# RasPi-BplusHAT.net
KiCad netlist of a schematic drawn in EAGLE
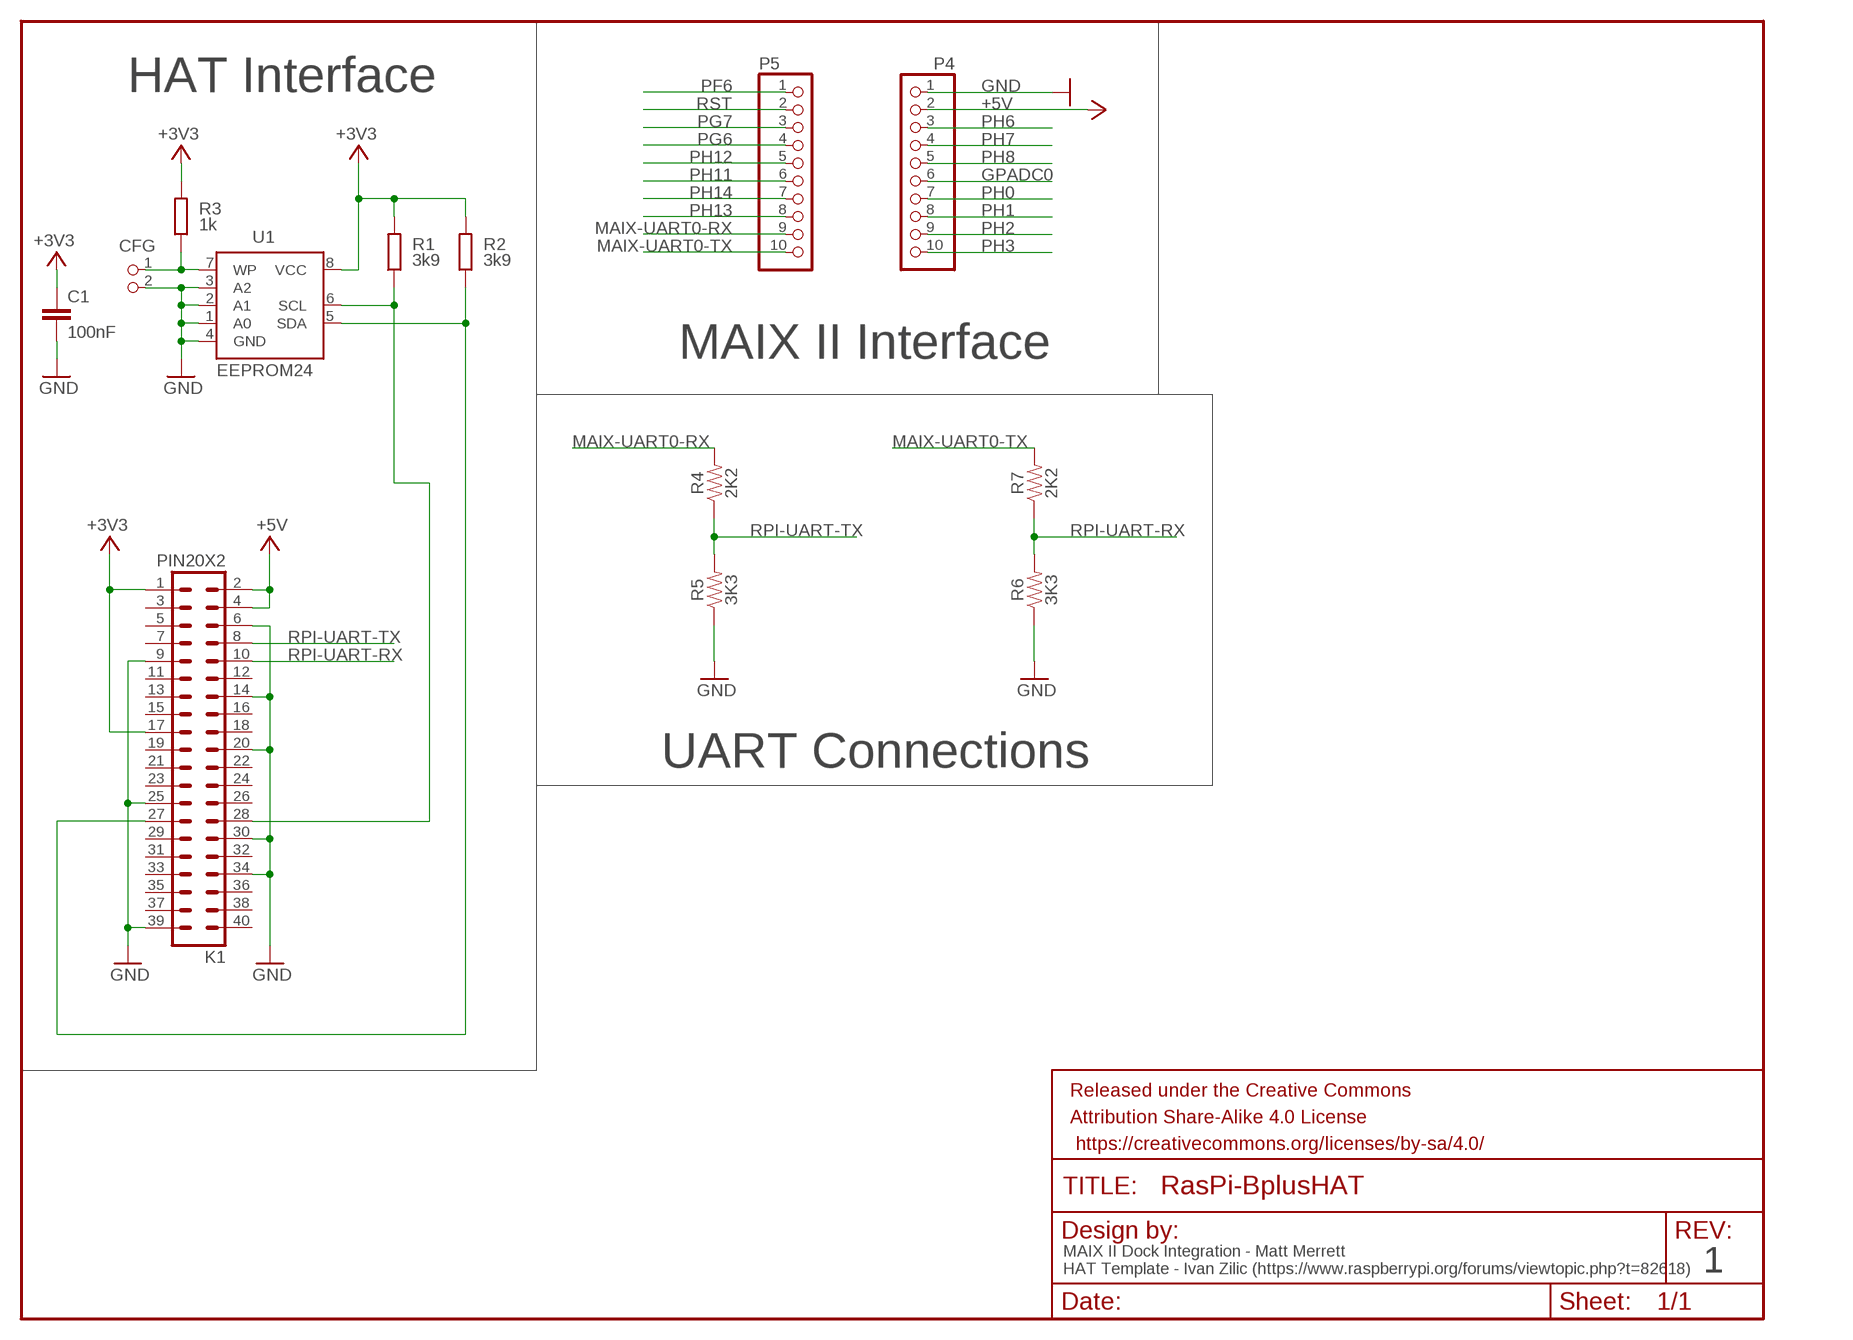
[diagram p0: schematic, sheet 1]

(export (version "E")
  (design (tool "Eeschema 10.0.6"))
  (components
    (comp (ref "C1")
      (value "100nF")
      (footprint "eagle-import:C0805K")
      (libsource (lib "eagle-import") (part "C-EUC0805K"))
    )
    (comp (ref "CFG")
      (value "PIN2_100")
      (footprint "eagle-import:PIN_W_2")
      (libsource (lib "eagle-import") (part "PIN2_100"))
    )
    (comp (ref "FRAME1")
      (value "FRAME-LETTER")
      (footprint "eagle-import:CREATIVE_COMMONS")
      (libsource (lib "eagle-import") (part "FRAME-LETTER"))
    )
    (comp (ref "K1")
      (value "PIN20X2")
      (footprint "eagle-import:PIN_20X2")
      (libsource (lib "eagle-import") (part "PIN20X2"))
    )
    (comp (ref "P4")
      (value "PINHD-1X10")
      (footprint "eagle-import:1X10")
      (libsource (lib "eagle-import") (part "PINHD-1X10"))
    )
    (comp (ref "P5")
      (value "PINHD-1X10")
      (footprint "eagle-import:1X10")
      (libsource (lib "eagle-import") (part "PINHD-1X10"))
    )
    (comp (ref "R1")
      (value "3k9")
      (footprint "eagle-import:M0805")
      (fields (field (name "TOLERANCE") "5%"))
      (libsource (lib "eagle-import") (part "R-EU_M0805"))
    )
    (comp (ref "R2")
      (value "3k9")
      (footprint "eagle-import:M0805")
      (fields (field (name "TOLERANCE") "5%"))
      (libsource (lib "eagle-import") (part "R-EU_M0805"))
    )
    (comp (ref "R3")
      (value "1k")
      (footprint "eagle-import:M0805")
      (fields (field (name "TOLERANCE") "5%"))
      (libsource (lib "eagle-import") (part "R-EU_M0805"))
    )
    (comp (ref "R4")
      (value "2K2")
      (footprint "eagle-import:AXIAL-0.3")
      (libsource (lib "eagle-import") (part "RESISTORAXIAL-0.3"))
    )
    (comp (ref "R5")
      (value "3K3")
      (footprint "eagle-import:AXIAL-0.3")
      (libsource (lib "eagle-import") (part "RESISTORAXIAL-0.3"))
    )
    (comp (ref "R6")
      (value "3K3")
      (footprint "eagle-import:AXIAL-0.3")
      (libsource (lib "eagle-import") (part "RESISTORAXIAL-0.3"))
    )
    (comp (ref "R7")
      (value "2K2")
      (footprint "eagle-import:AXIAL-0.3")
      (libsource (lib "eagle-import") (part "RESISTORAXIAL-0.3"))
    )
    (comp (ref "U1")
      (value "EEPROM24")
      (footprint "eagle-import:SOIC8")
      (libsource (lib "eagle-import") (part "EEPROM24"))
    )
  )
  (nets
    (net (code "1") (name "+3V3") (class "Default")
      (node (ref "C1") (pin "1") (pinfunction "1_1") (pintype "passive"))
      (node (ref "K1") (pin "1") (pinfunction "1_1") (pintype "passive"))
      (node (ref "K1") (pin "17") (pinfunction "17_17") (pintype "passive"))
      (node (ref "R1") (pin "2") (pinfunction "2_2") (pintype "passive"))
      (node (ref "R2") (pin "2") (pinfunction "2_2") (pintype "passive"))
      (node (ref "R3") (pin "2") (pinfunction "2_2") (pintype "passive"))
      (node (ref "U1") (pin "8") (pinfunction "VCC_8") (pintype "power_in"))
    )
    (net (code "2") (name "+5V") (class "Default")
      (node (ref "K1") (pin "2") (pinfunction "2_2") (pintype "passive"))
      (node (ref "K1") (pin "4") (pinfunction "4_4") (pintype "passive"))
      (node (ref "P4") (pin "2") (pinfunction "2_2") (pintype "passive"))
    )
    (net (code "3") (name "/GPADC0") (class "Default")
      (node (ref "P4") (pin "6") (pinfunction "6_6") (pintype "passive"))
    )
    (net (code "4") (name "/MAIX-UART0-RX") (class "Default")
      (node (ref "P5") (pin "9") (pinfunction "9_9") (pintype "passive"))
      (node (ref "R4") (pin "P$2") (pinfunction "2_P$2") (pintype "passive"))
    )
    (net (code "5") (name "/MAIX-UART0-TX") (class "Default")
      (node (ref "P5") (pin "10") (pinfunction "10_10") (pintype "passive"))
      (node (ref "R7") (pin "P$2") (pinfunction "2_P$2") (pintype "passive"))
    )
    (net (code "6") (name "/PF6") (class "Default")
      (node (ref "P5") (pin "1") (pinfunction "1_1") (pintype "passive"))
    )
    (net (code "7") (name "/PG6") (class "Default")
      (node (ref "P5") (pin "4") (pinfunction "4_4") (pintype "passive"))
    )
    (net (code "8") (name "/PG7") (class "Default")
      (node (ref "P5") (pin "3") (pinfunction "3_3") (pintype "passive"))
    )
    (net (code "9") (name "/PH0") (class "Default")
      (node (ref "P4") (pin "7") (pinfunction "7_7") (pintype "passive"))
    )
    (net (code "10") (name "/PH1") (class "Default")
      (node (ref "P4") (pin "8") (pinfunction "8_8") (pintype "passive"))
    )
    (net (code "11") (name "/PH2") (class "Default")
      (node (ref "P4") (pin "9") (pinfunction "9_9") (pintype "passive"))
    )
    (net (code "12") (name "/PH3") (class "Default")
      (node (ref "P4") (pin "10") (pinfunction "10_10") (pintype "passive"))
    )
    (net (code "13") (name "/PH6") (class "Default")
      (node (ref "P4") (pin "3") (pinfunction "3_3") (pintype "passive"))
    )
    (net (code "14") (name "/PH7") (class "Default")
      (node (ref "P4") (pin "4") (pinfunction "4_4") (pintype "passive"))
    )
    (net (code "15") (name "/PH8") (class "Default")
      (node (ref "P4") (pin "5") (pinfunction "5_5") (pintype "passive"))
    )
    (net (code "16") (name "/PH11") (class "Default")
      (node (ref "P5") (pin "6") (pinfunction "6_6") (pintype "passive"))
    )
    (net (code "17") (name "/PH12") (class "Default")
      (node (ref "P5") (pin "5") (pinfunction "5_5") (pintype "passive"))
    )
    (net (code "18") (name "/PH13") (class "Default")
      (node (ref "P5") (pin "8") (pinfunction "8_8") (pintype "passive"))
    )
    (net (code "19") (name "/PH14") (class "Default")
      (node (ref "P5") (pin "7") (pinfunction "7_7") (pintype "passive"))
    )
    (net (code "20") (name "/RPI-UART-RX") (class "Default")
      (node (ref "K1") (pin "10") (pinfunction "10_10") (pintype "passive"))
      (node (ref "R6") (pin "P$2") (pinfunction "2_P$2") (pintype "passive"))
      (node (ref "R7") (pin "P$1") (pinfunction "1_P$1") (pintype "passive"))
    )
    (net (code "21") (name "/RPI-UART-TX") (class "Default")
      (node (ref "K1") (pin "8") (pinfunction "8_8") (pintype "passive"))
      (node (ref "R4") (pin "P$1") (pinfunction "1_P$1") (pintype "passive"))
      (node (ref "R5") (pin "P$2") (pinfunction "2_P$2") (pintype "passive"))
    )
    (net (code "22") (name "/RST") (class "Default")
      (node (ref "P5") (pin "2") (pinfunction "2_2") (pintype "passive"))
    )
    (net (code "23") (name "GND") (class "Default")
      (node (ref "C1") (pin "2") (pinfunction "2_2") (pintype "passive"))
      (node (ref "CFG") (pin "2") (pinfunction "2_2") (pintype "passive"))
      (node (ref "K1") (pin "14") (pinfunction "14_14") (pintype "passive"))
      (node (ref "K1") (pin "20") (pinfunction "20_20") (pintype "passive"))
      (node (ref "K1") (pin "25") (pinfunction "25_25") (pintype "passive"))
      (node (ref "K1") (pin "30") (pinfunction "30_30") (pintype "passive"))
      (node (ref "K1") (pin "34") (pinfunction "34_34") (pintype "passive"))
      (node (ref "K1") (pin "39") (pinfunction "39_39") (pintype "passive"))
      (node (ref "K1") (pin "6") (pinfunction "6_6") (pintype "passive"))
      (node (ref "K1") (pin "9") (pinfunction "9_9") (pintype "passive"))
      (node (ref "P4") (pin "1") (pinfunction "1_1") (pintype "passive"))
      (node (ref "R5") (pin "P$1") (pinfunction "1_P$1") (pintype "passive"))
      (node (ref "R6") (pin "P$1") (pinfunction "1_P$1") (pintype "passive"))
      (node (ref "U1") (pin "1") (pinfunction "A0_1") (pintype "input"))
      (node (ref "U1") (pin "2") (pinfunction "A1_2") (pintype "input"))
      (node (ref "U1") (pin "3") (pinfunction "A2_3") (pintype "input"))
      (node (ref "U1") (pin "4") (pinfunction "GND_4") (pintype "power_in"))
    )
    (net (code "24") (name "Net-(U1-SCL)") (class "Default")
      (node (ref "K1") (pin "28") (pinfunction "28_28") (pintype "passive"))
      (node (ref "R1") (pin "1") (pinfunction "1_1") (pintype "passive"))
      (node (ref "U1") (pin "6") (pinfunction "SCL_6") (pintype "input"))
    )
    (net (code "25") (name "Net-(U1-SDA)") (class "Default")
      (node (ref "K1") (pin "27") (pinfunction "27_27") (pintype "passive"))
      (node (ref "R2") (pin "1") (pinfunction "1_1") (pintype "passive"))
      (node (ref "U1") (pin "5") (pinfunction "SDA_5") (pintype "bidirectional"))
    )
    (net (code "26") (name "Net-(U1-WP)") (class "Default")
      (node (ref "CFG") (pin "1") (pinfunction "1_1") (pintype "passive"))
      (node (ref "R3") (pin "1") (pinfunction "1_1") (pintype "passive"))
      (node (ref "U1") (pin "7") (pinfunction "WP_7") (pintype "input"))
    )
    (net (code "27") (name "unconnected-(K1-Pad3)") (class "Default")
      (node (ref "K1") (pin "3") (pinfunction "3_3") (pintype "passive"))
    )
    (net (code "28") (name "unconnected-(K1-Pad5)") (class "Default")
      (node (ref "K1") (pin "5") (pinfunction "5_5") (pintype "passive"))
    )
    (net (code "29") (name "unconnected-(K1-Pad7)") (class "Default")
      (node (ref "K1") (pin "7") (pinfunction "7_7") (pintype "passive"))
    )
    (net (code "30") (name "unconnected-(K1-Pad11)") (class "Default")
      (node (ref "K1") (pin "11") (pinfunction "11_11") (pintype "passive"))
    )
    (net (code "31") (name "unconnected-(K1-Pad12)") (class "Default")
      (node (ref "K1") (pin "12") (pinfunction "12_12") (pintype "passive"))
    )
    (net (code "32") (name "unconnected-(K1-Pad13)") (class "Default")
      (node (ref "K1") (pin "13") (pinfunction "13_13") (pintype "passive"))
    )
    (net (code "33") (name "unconnected-(K1-Pad15)") (class "Default")
      (node (ref "K1") (pin "15") (pinfunction "15_15") (pintype "passive"))
    )
    (net (code "34") (name "unconnected-(K1-Pad16)") (class "Default")
      (node (ref "K1") (pin "16") (pinfunction "16_16") (pintype "passive"))
    )
    (net (code "35") (name "unconnected-(K1-Pad18)") (class "Default")
      (node (ref "K1") (pin "18") (pinfunction "18_18") (pintype "passive"))
    )
    (net (code "36") (name "unconnected-(K1-Pad19)") (class "Default")
      (node (ref "K1") (pin "19") (pinfunction "19_19") (pintype "passive"))
    )
    (net (code "37") (name "unconnected-(K1-Pad21)") (class "Default")
      (node (ref "K1") (pin "21") (pinfunction "21_21") (pintype "passive"))
    )
    (net (code "38") (name "unconnected-(K1-Pad22)") (class "Default")
      (node (ref "K1") (pin "22") (pinfunction "22_22") (pintype "passive"))
    )
    (net (code "39") (name "unconnected-(K1-Pad23)") (class "Default")
      (node (ref "K1") (pin "23") (pinfunction "23_23") (pintype "passive"))
    )
    (net (code "40") (name "unconnected-(K1-Pad24)") (class "Default")
      (node (ref "K1") (pin "24") (pinfunction "24_24") (pintype "passive"))
    )
    (net (code "41") (name "unconnected-(K1-Pad26)") (class "Default")
      (node (ref "K1") (pin "26") (pinfunction "26_26") (pintype "passive"))
    )
    (net (code "42") (name "unconnected-(K1-Pad29)") (class "Default")
      (node (ref "K1") (pin "29") (pinfunction "29_29") (pintype "passive"))
    )
    (net (code "43") (name "unconnected-(K1-Pad31)") (class "Default")
      (node (ref "K1") (pin "31") (pinfunction "31_31") (pintype "passive"))
    )
    (net (code "44") (name "unconnected-(K1-Pad32)") (class "Default")
      (node (ref "K1") (pin "32") (pinfunction "32_32") (pintype "passive"))
    )
    (net (code "45") (name "unconnected-(K1-Pad33)") (class "Default")
      (node (ref "K1") (pin "33") (pinfunction "33_33") (pintype "passive"))
    )
    (net (code "46") (name "unconnected-(K1-Pad35)") (class "Default")
      (node (ref "K1") (pin "35") (pinfunction "35_35") (pintype "passive"))
    )
    (net (code "47") (name "unconnected-(K1-Pad36)") (class "Default")
      (node (ref "K1") (pin "36") (pinfunction "36_36") (pintype "passive"))
    )
    (net (code "48") (name "unconnected-(K1-Pad37)") (class "Default")
      (node (ref "K1") (pin "37") (pinfunction "37_37") (pintype "passive"))
    )
    (net (code "49") (name "unconnected-(K1-Pad38)") (class "Default")
      (node (ref "K1") (pin "38") (pinfunction "38_38") (pintype "passive"))
    )
    (net (code "50") (name "unconnected-(K1-Pad40)") (class "Default")
      (node (ref "K1") (pin "40") (pinfunction "40_40") (pintype "passive"))
    )
  )
)
